# SWG.net
KiCad netlist of a schematic drawn in Altium Designer
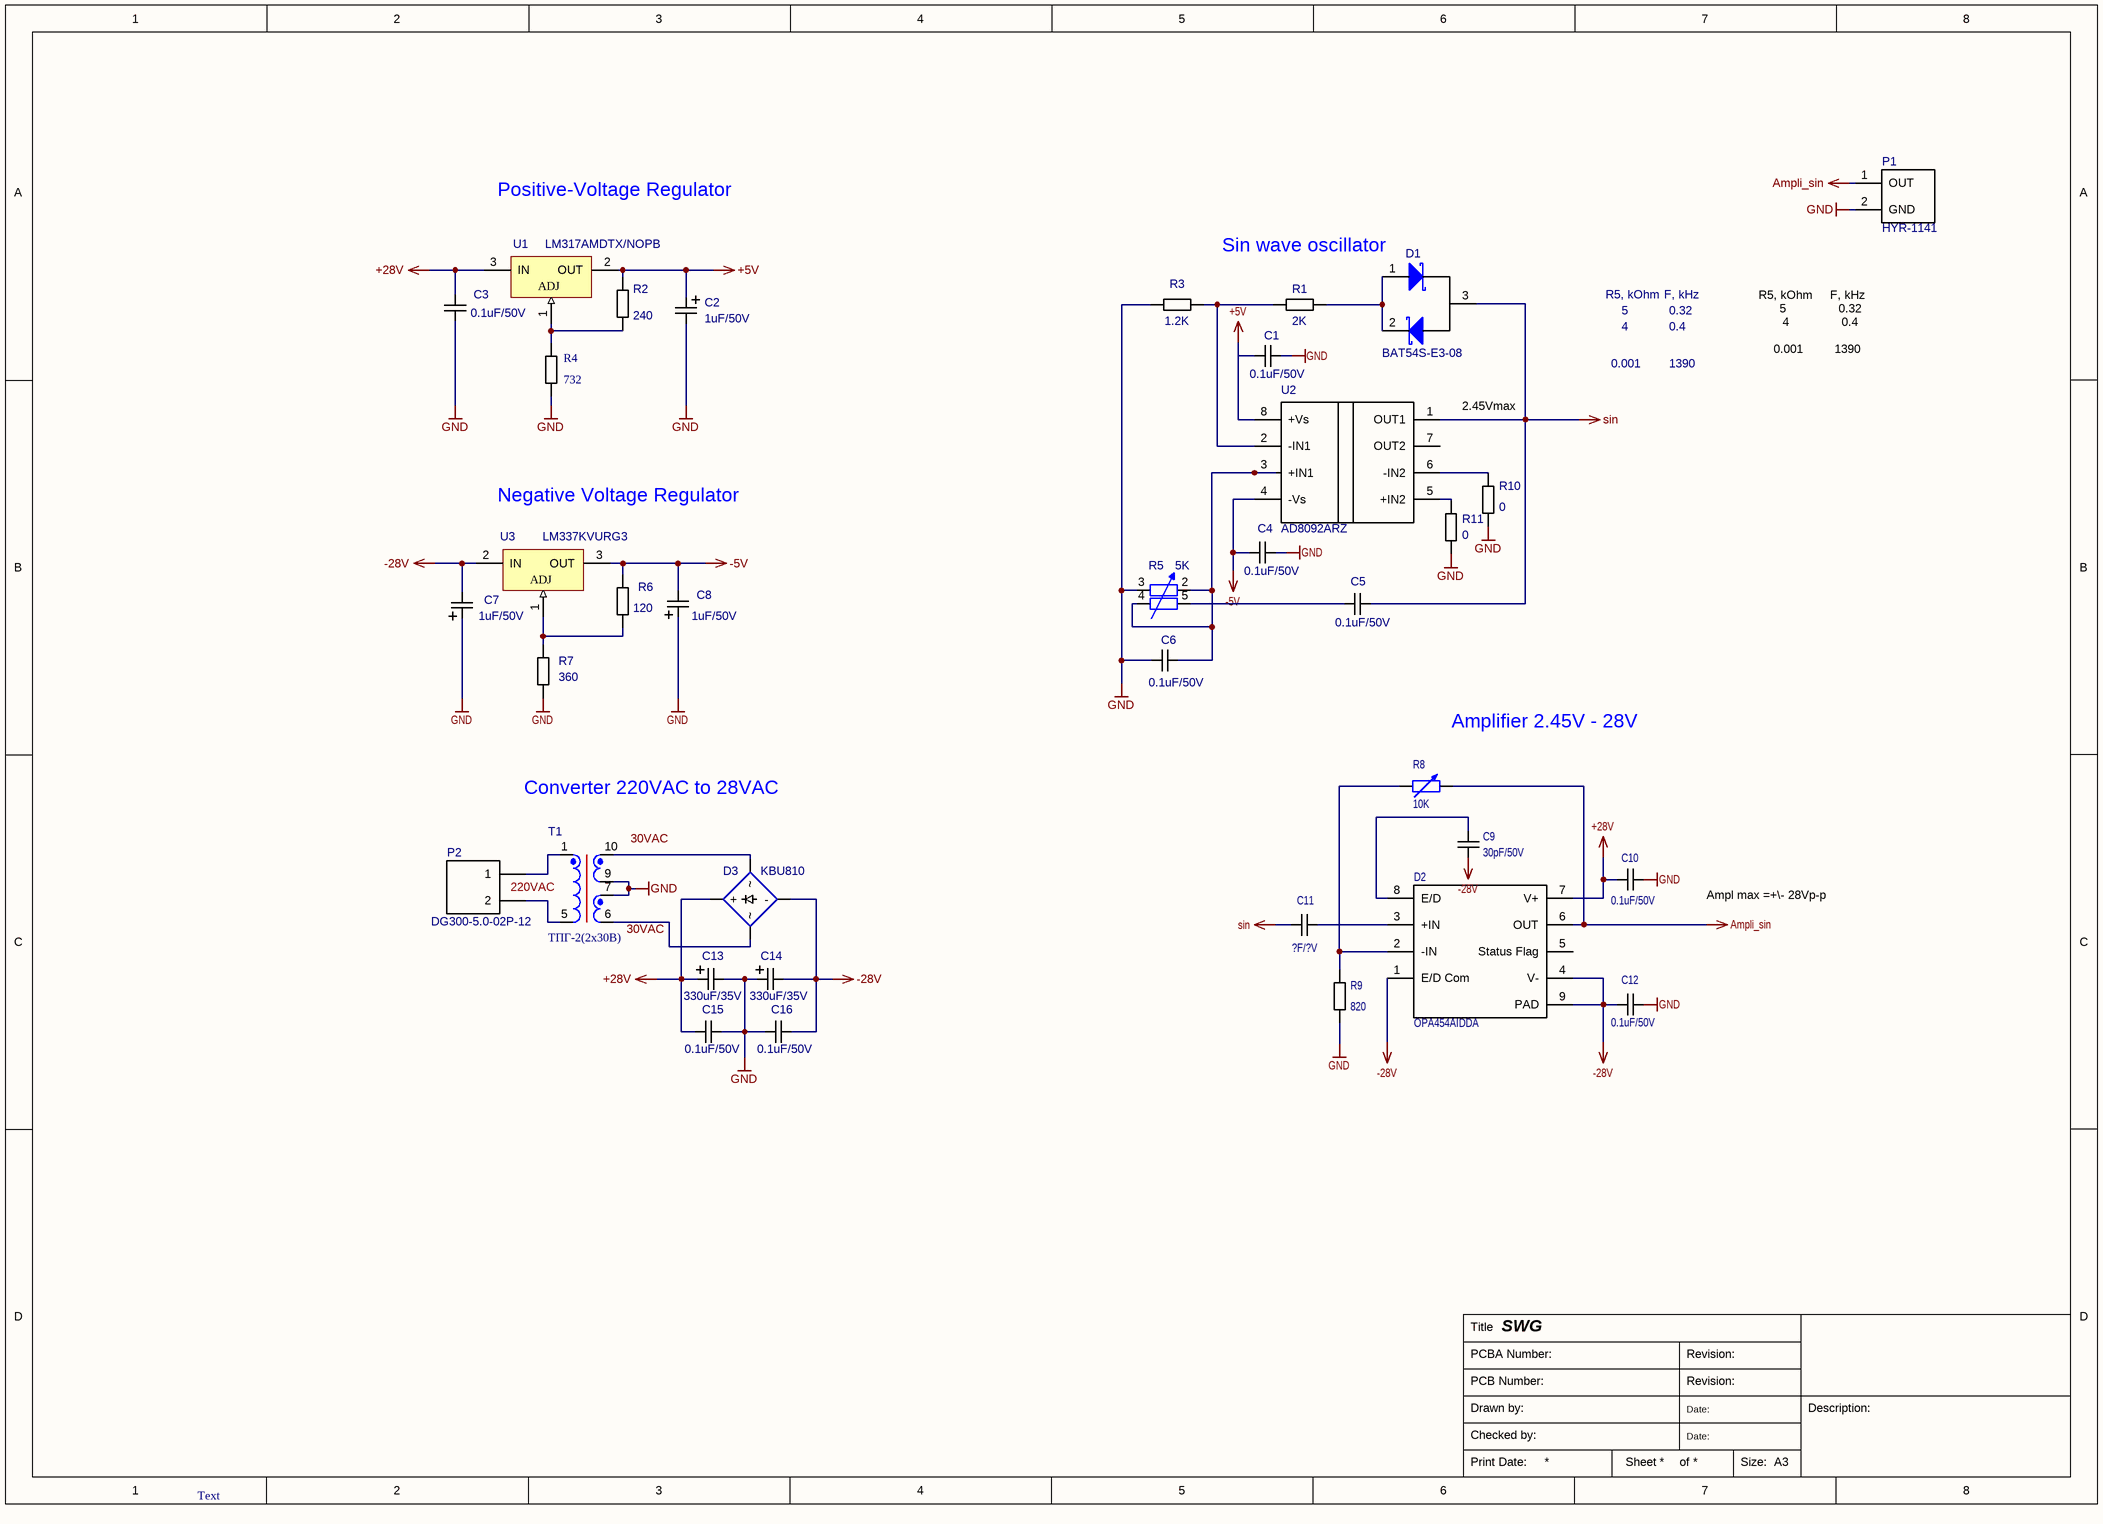
[diagram p0: SWG.SchDoc]

(export (version "E")
  (design (tool "Eeschema 10.0.6"))
  (components
    (comp (ref "C1")
      (value "0.1uF/50V")
      (footprint "C0603")
      (description "Ceramic chip capacitor. 0.1 UF X7R 50V 10% 0603")
      (fields
        (field (name "MANUFACTURER") "Murata Manufacturing")
        (field (name "PARTNUMBER") "GRM188R71H104KA93D")
      )
      (libsource (lib "Schlib_SIN_GEN") (part "CAP_0603_0.1uF/50V"))
    )
    (comp (ref "C2")
      (value "1uF/50V")
      (footprint "UCHEMI-CON_CAP0404_RAD")
      (description "Electrolytic smd capacitor 1 UF 50V")
      (fields (field (name "MANUFACTURER") "JB") (field (name "PARTNUMBER") "JCK1H010M040054"))
      (libsource (lib "Schlib_SIN_GEN") (part "CAP_electrolit_1uf"))
    )
    (comp (ref "C3")
      (value "0.1uF/50V")
      (footprint "C0603")
      (description "Ceramic chip capacitor. 0.1 UF X7R 50V 10% 0603")
      (fields
        (field (name "MANUFACTURER") "Murata Manufacturing")
        (field (name "PARTNUMBER") "GRM188R71H104KA93D")
      )
      (libsource (lib "Schlib_SIN_GEN") (part "CAP_0603_0.1uF/50V"))
    )
    (comp (ref "C4")
      (value "0.1uF/50V")
      (footprint "C0603")
      (description "Ceramic chip capacitor. 0.1 UF X7R 50V 10% 0603")
      (fields
        (field (name "MANUFACTURER") "Murata Manufacturing")
        (field (name "PARTNUMBER") "GRM188R71H104KA93D")
      )
      (libsource (lib "Schlib_SIN_GEN") (part "CAP_0603_0.1uF/50V"))
    )
    (comp (ref "C5")
      (value "0.1uF/50V")
      (footprint "C0603")
      (fields
        (field (name "MANUFACTURER") "Murata Manufacturing")
        (field (name "PARTNUMBER") "GRM188R71H104KA93D")
      )
      (libsource (lib "Schlib_SIN_GEN") (part "CAP_0603_0.1F/50V"))
    )
    (comp (ref "C6")
      (value "0.1uF/50V")
      (footprint "C0603")
      (description "Ceramic chip capacitor. 0.1 UF X7R 50V 10% 0603")
      (fields
        (field (name "MANUFACTURER") "Murata Manufacturing")
        (field (name "PARTNUMBER") "GRM188R71H104KA93D")
      )
      (libsource (lib "Schlib_SIN_GEN") (part "CAP_0603_0.1uF/50V"))
    )
    (comp (ref "C7")
      (value "1uF/50V")
      (footprint "UCHEMI-CON_CAP0404_RAD")
      (description "Electrolytic smd capacitor 1 UF 50V")
      (fields (field (name "MANUFACTURER") "JB") (field (name "PARTNUMBER") "JCK1H010M040054"))
      (libsource (lib "Schlib_SIN_GEN") (part "CAP_electrolit_1uf"))
    )
    (comp (ref "C8")
      (value "1uF/50V")
      (footprint "UCHEMI-CON_CAP0404_RAD")
      (description "Electrolytic smd capacitor 1 UF 50V")
      (fields (field (name "MANUFACTURER") "JB") (field (name "PARTNUMBER") "JCK1H010M040054"))
      (libsource (lib "Schlib_SIN_GEN") (part "CAP_electrolit_1uf"))
    )
    (comp (ref "C9")
      (value "30pF/50V")
      (footprint "C0603")
      (fields
        (field (name "MANUFACTURER") "Murata Manufacturing")
        (field (name "PARTNUMBER") "GRM2165C1H300JZ01D")
      )
      (libsource (lib "Schlib_SIN_GEN") (part "CAP_0603_30pF/50V"))
    )
    (comp (ref "C10")
      (value "0.1uF/50V")
      (footprint "C0603")
      (description "Ceramic chip capacitor. 0.1 UF X7R 50V 10% 0603")
      (fields
        (field (name "MANUFACTURER") "Murata Manufacturing")
        (field (name "PARTNUMBER") "GRM188R71H104KA93D")
      )
      (libsource (lib "Schlib_SIN_GEN") (part "CAP_0603_0.1F/50V"))
    )
    (comp (ref "C11")
      (value "?F/?V")
      (footprint "C0603")
      (fields (field (name "MANUFACTURER") "Murata Manufacturing") (field (name "PARTNUMBER") "?"))
      (libsource (lib "Schlib_SIN_GEN") (part "CAP_0603_?F/?V"))
    )
    (comp (ref "C12")
      (value "0.1uF/50V")
      (footprint "C0603")
      (description "Ceramic chip capacitor. 0.1 UF X7R 50V 10% 0603")
      (fields
        (field (name "MANUFACTURER") "Murata Manufacturing")
        (field (name "PARTNUMBER") "GRM188R71H104KA93D")
      )
      (libsource (lib "Schlib_SIN_GEN") (part "CAP_0603_0.1F/50V"))
    )
    (comp (ref "C13")
      (value "330uF/35V")
      (footprint "UCHEMI-CON_CAP1010_RAD")
      (fields (field (name "MANUFACTURER") "JB") (field (name "PARTNUMBER") "JCK1V331M100105"))
      (libsource (lib "Schlib_SIN_GEN") (part "CAP_electrolit_330uf"))
    )
    (comp (ref "C14")
      (value "330uF/35V")
      (footprint "UCHEMI-CON_CAP1010_RAD")
      (fields (field (name "MANUFACTURER") "JB") (field (name "PARTNUMBER") "JCK1V331M100105"))
      (libsource (lib "Schlib_SIN_GEN") (part "CAP_electrolit_330uf"))
    )
    (comp (ref "C15")
      (value "0.1uF/50V")
      (footprint "C0603")
      (description "Ceramic chip capacitor. 0.1 UF X7R 50V 10% 0603")
      (fields
        (field (name "MANUFACTURER") "Murata Manufacturing")
        (field (name "PARTNUMBER") "GRM188R71H104KA93D")
      )
      (libsource (lib "Schlib_SIN_GEN") (part "CAP_0603_0.1F/50V"))
    )
    (comp (ref "C16")
      (value "0.1uF/50V")
      (footprint "C0603")
      (description "Ceramic chip capacitor. 0.1 UF X7R 50V 10% 0603")
      (fields
        (field (name "MANUFACTURER") "Murata Manufacturing")
        (field (name "PARTNUMBER") "GRM188R71H104KA93D")
      )
      (libsource (lib "Schlib_SIN_GEN") (part "CAP_0603_0.1F/50V"))
    )
    (comp (ref "D1")
      (value "BAT54S-E3-08")
      (footprint "SOT23-3L")
      (description "Dual Schottky Rectifier, SOT-23, 30V 200mA")
      (fields (field (name "MANUFACTURER") "Vishay"))
      (libsource (lib "Schlib_SIN_GEN") (part "Diode BAT54S"))
    )
    (comp (ref "D2")
      (value "OPA454AIDDA")
      (footprint "TI_8SOICPAD")
      (description "IC OPAMP GP 1 CIRCUIT 8SOPWRPAD")
      (fields (field (name "MANUFACTURER") "Texas Instruments"))
      (libsource (lib "Schlib_SIN_GEN") (part "CH_OPA454AIDDA"))
    )
    (comp (ref "D3")
      (value "KBU810")
      (footprint "KBU8")
      (description "KBU8 series bridge single-phase rectifier, 8А, 1000V")
      (fields (field (name "MANUFACTURER") "China"))
      (libsource (lib "Schlib_SIN_GEN") (part "KBU810"))
    )
    (comp (ref "P1")
      (value "HYR-1141")
      (footprint "SMA")
      (fields (field (name "MANUFACTURER") "New Centress (HOYUTEC)"))
      (libsource (lib "Schlib_SIN_GEN") (part "SMA"))
    )
    (comp (ref "P2")
      (value "DG300-5.0-02P-12")
      (footprint "DG300-5.0-02P-12")
      (fields (field (name "MANUFACTURER") "Degson Electronics"))
      (libsource (lib "Schlib_SIN_GEN") (part "DG300-5.0-02P-12"))
    )
    (comp (ref "R1")
      (value "2K")
      (footprint "R0603")
      (fields (field (name "MANUFACTURER") "Yageo") (field (name "PARTNUMBER") "RC0603FR-0744K2L"))
      (libsource (lib "Schlib_SIN_GEN") (part "RES_0603_2K"))
    )
    (comp (ref "R2")
      (value "240")
      (footprint "SWG:R0603")
      (description "RES SMD 240 OHM 1% 1/10W 0603")
      (fields
        (field (name "MANUFACTURER") "Panasonic Electronic Components")
        (field (name "PARTNUMBER") "ERJ-3EKF2400V")
      )
      (libsource (lib "SWG") (part "RES_0402_240"))
    )
    (comp (ref "R3")
      (value "1.2K")
      (footprint "R0603")
      (fields (field (name "MANUFACTURER") "Yageo") (field (name "PARTNUMBER") "RC0603FR-071K2L"))
      (libsource (lib "Schlib_SIN_GEN") (part "RES_0603_1.2K"))
    )
    (comp (ref "R4")
      (value "732")
      (footprint "SWG:R0603")
      (description "RES SMD 732 OHM 1% 1/10W 0603")
      (fields
        (field (name "MANUFACTURER") "Panasonic Electronic Components")
        (field (name "PARTNUMBER") "ERJ-3EKF7320V")
      )
      (libsource (lib "SWG") (part "RES_0402_732"))
    )
    (comp (ref "R5")
      (value "5K")
      (footprint "RES_Adj_duble_5K")
      (description "Dual variable resistor WH148-2, resistance nominal 5kom. Metal handle with a recess for the cap.")
      (fields (field (name "PARTNUMBER") "WH148-2") (field (name "MANUFACTURER") "China"))
      (libsource (lib "Schlib_SIN_GEN") (part "RES_Adj_duble_5K"))
    )
    (comp (ref "R6")
      (value "120")
      (footprint "SWG:R0603")
      (fields
        (field (name "MANUFACTURER") "Panasonic Electronic Components Panasonic Electronic Components")
        (field (name "PARTNUMBER") "ERJ-2RKF1200X")
        (field (name "TOLERANCE") "±1%")
      )
      (libsource (lib "SWG") (part "RES_0402"))
    )
    (comp (ref "R7")
      (value "360")
      (footprint "SWG:R0603")
      (description "RES SMD 360 OHM 1% 1/10W 0603")
      (fields
        (field (name "MANUFACTURER") "Panasonic Electronic Components")
        (field (name "PARTNUMBER") "ERJ-3EKF3600V")
      )
      (libsource (lib "SWG") (part "RES_0402"))
    )
    (comp (ref "R8")
      (value "10K")
      (footprint "RES_Adj_10K")
      (description "Variable Resistor")
      (fields (field (name "PARTNUMBER") "16K1-10C10K,L15KC") (field (name "MANUFACTURER") "China"))
      (libsource (lib "Schlib_SIN_GEN") (part "Res_Adj_10K"))
    )
    (comp (ref "R9")
      (value "820")
      (footprint "R0603")
      (fields (field (name "MANUFACTURER") "Yageo") (field (name "PARTNUMBER") "RC0603FR-07820RL"))
      (libsource (lib "Schlib_SIN_GEN") (part "RES_0603_820"))
    )
    (comp (ref "R10")
      (value "0")
      (footprint "R0603")
      (fields (field (name "MANUFACTURER") "Yageo") (field (name "PARTNUMBER") "RC0603JR-070RL"))
      (libsource (lib "Schlib_SIN_GEN") (part "RES_0603_0"))
    )
    (comp (ref "R11")
      (value "0")
      (footprint "R0603")
      (fields (field (name "MANUFACTURER") "Yageo") (field (name "PARTNUMBER") "RC0603JR-070RL"))
      (libsource (lib "Schlib_SIN_GEN") (part "RES_0603_0"))
    )
    (comp (ref "T1")
      (value "ТПГ-2(2х30В)")
      (footprint "ТПГ-2 (2x30)")
      (description "Sealed transformer")
      (fields (field (name "MANUFACTURER") "Комплекс"))
      (libsource (lib "Schlib_SIN_GEN") (part "ТПГ-2 (2x30)"))
    )
    (comp (ref "U1")
      (value "LM317AMDTX/NOPB")
      (footprint "SC_TO-252A")
      (description "3-Terminal Adjustable Regulator")
      (fields (field (name "MANUFACTURER") "Texas Instruments"))
      (libsource (lib "Schlib_SIN_GEN") (part "LM317AMDTX/NOPB"))
    )
    (comp (ref "U2")
      (value "AD8092ARZ")
      (footprint "AD_SOIC-8_R-8_Rev4")
      (fields (field (name "MANUFACTURER") "Analog Devices"))
      (libsource (lib "Schlib_SIN_GEN") (part "AD8092ARZ_1"))
    )
    (comp (ref "U3")
      (value "LM337KVURG3")
      (footprint "SC_TO-252A")
      (description "3-Terminal Adjustable Negative Regulator")
      (fields (field (name "MANUFACTURER") "Texas Instruments"))
      (libsource (lib "Schlib_SIN_GEN") (part "LM337KVURG3"))
    )
  )
  (nets
    (net (code "1") (name "+5V") (class "Default")
      (node (ref "C1") (pin "1") (pinfunction "1_1") (pintype "passive"))
      (node (ref "C2") (pin "1") (pinfunction "+_1") (pintype "passive"))
      (node (ref "R2") (pin "2") (pinfunction "2_2") (pintype "passive"))
      (node (ref "U1") (pin "2") (pinfunction "OUT_2") (pintype "power_in"))
      (node (ref "U2") (pin "8") (pinfunction "+Vs_8") (pintype "passive"))
    )
    (net (code "2") (name "+28V") (class "Default")
      (node (ref "C10") (pin "1") (pinfunction "1_1") (pintype "passive"))
      (node (ref "C13") (pin "1") (pinfunction "+_1") (pintype "passive"))
      (node (ref "C15") (pin "1") (pinfunction "1_1") (pintype "passive"))
      (node (ref "C3") (pin "2") (pinfunction "2_2") (pintype "passive"))
      (node (ref "D2") (pin "7") (pinfunction "V+_7") (pintype "passive"))
      (node (ref "D3") (pin "1") (pinfunction "+_1") (pintype "passive"))
      (node (ref "U1") (pin "3") (pinfunction "IN_3") (pintype "power_in"))
    )
    (net (code "3") (name "-5V") (class "Default")
      (node (ref "C4") (pin "1") (pinfunction "1_1") (pintype "passive"))
      (node (ref "C8") (pin "2") (pinfunction "-_2") (pintype "passive"))
      (node (ref "R6") (pin "2") (pinfunction "2_2") (pintype "passive"))
      (node (ref "U2") (pin "4") (pinfunction "-Vs_4") (pintype "passive"))
      (node (ref "U3") (pin "3") (pinfunction "OUT_3") (pintype "power_in"))
    )
    (net (code "4") (name "-28V") (class "Default")
      (node (ref "C12") (pin "1") (pinfunction "1_1") (pintype "passive"))
      (node (ref "C14") (pin "2") (pinfunction "-_2") (pintype "passive"))
      (node (ref "C16") (pin "2") (pinfunction "2_2") (pintype "passive"))
      (node (ref "C7") (pin "2") (pinfunction "-_2") (pintype "passive"))
      (node (ref "C9") (pin "2") (pinfunction "2_2") (pintype "passive"))
      (node (ref "D2") (pin "1") (pinfunction "E/D_Com_1") (pintype "passive"))
      (node (ref "D2") (pin "4") (pinfunction "V-_4") (pintype "passive"))
      (node (ref "D2") (pin "9") (pinfunction "PAD_9") (pintype "passive"))
      (node (ref "D3") (pin "4") (pinfunction "-_4") (pintype "passive"))
      (node (ref "U3") (pin "2") (pinfunction "IN_2") (pintype "power_in"))
    )
    (net (code "6") (name "Ampli_sin") (class "Default")
      (node (ref "D2") (pin "6") (pinfunction "OUT_6") (pintype "passive"))
      (node (ref "P1") (pin "1") (pinfunction "OUT_1") (pintype "passive"))
      (node (ref "R8") (pin "2") (pinfunction "2_2") (pintype "passive"))
    )
    (net (code "7") (name "GND") (class "Default")
      (node (ref "C1") (pin "2") (pinfunction "2_2") (pintype "passive"))
      (node (ref "C10") (pin "2") (pinfunction "2_2") (pintype "passive"))
      (node (ref "C12") (pin "2") (pinfunction "2_2") (pintype "passive"))
      (node (ref "C13") (pin "2") (pinfunction "-_2") (pintype "passive"))
      (node (ref "C14") (pin "1") (pinfunction "+_1") (pintype "passive"))
      (node (ref "C15") (pin "2") (pinfunction "2_2") (pintype "passive"))
      (node (ref "C16") (pin "1") (pinfunction "1_1") (pintype "passive"))
      (node (ref "C2") (pin "2") (pinfunction "-_2") (pintype "passive"))
      (node (ref "C3") (pin "1") (pinfunction "1_1") (pintype "passive"))
      (node (ref "C4") (pin "2") (pinfunction "2_2") (pintype "passive"))
      (node (ref "C6") (pin "1") (pinfunction "1_1") (pintype "passive"))
      (node (ref "C7") (pin "1") (pinfunction "+_1") (pintype "passive"))
      (node (ref "C8") (pin "1") (pinfunction "+_1") (pintype "passive"))
      (node (ref "P1") (pin "2") (pinfunction "GND_2") (pintype "passive"))
      (node (ref "R10") (pin "2") (pinfunction "2_2") (pintype "passive"))
      (node (ref "R11") (pin "2") (pinfunction "2_2") (pintype "passive"))
      (node (ref "R3") (pin "1") (pinfunction "1_1") (pintype "passive"))
      (node (ref "R4") (pin "1") (pinfunction "1_1") (pintype "passive"))
      (node (ref "R5") (pin "3") (pinfunction "1_3") (pintype "passive"))
      (node (ref "R7") (pin "1") (pinfunction "1_1") (pintype "passive"))
      (node (ref "R9") (pin "1") (pinfunction "1_1") (pintype "passive"))
      (node (ref "T1") (pin "7") (pinfunction "7_7") (pintype "passive"))
      (node (ref "T1") (pin "9") (pinfunction "9_9") (pintype "passive"))
    )
    (net (code "8") (name "Net-(D1-A1)") (class "Default")
      (node (ref "D1") (pin "1") (pinfunction "A1_1") (pintype "passive"))
      (node (ref "D1") (pin "2") (pinfunction "K2_2") (pintype "passive"))
      (node (ref "R1") (pin "2") (pinfunction "2_2") (pintype "passive"))
    )
    (net (code "9") (name "Net-(D2-+IN)") (class "Default")
      (node (ref "C11") (pin "2") (pinfunction "2_2") (pintype "passive"))
      (node (ref "D2") (pin "3") (pinfunction "+IN_3") (pintype "passive"))
    )
    (net (code "10") (name "Net-(D2--IN)") (class "Default")
      (node (ref "D2") (pin "2") (pinfunction "-IN_2") (pintype "passive"))
      (node (ref "R8") (pin "1") (pinfunction "1_1") (pintype "passive"))
      (node (ref "R9") (pin "2") (pinfunction "2_2") (pintype "passive"))
    )
    (net (code "11") (name "Net-(D2-E{slash}D)") (class "Default")
      (node (ref "C9") (pin "1") (pinfunction "1_1") (pintype "passive"))
      (node (ref "D2") (pin "8") (pinfunction "E/D_8") (pintype "passive"))
    )
    (net (code "12") (name "Net-(D3-~-Pad2)") (class "Default")
      (node (ref "D3") (pin "2") (pinfunction "~_2") (pintype "passive"))
      (node (ref "T1") (pin "10") (pinfunction "10_10") (pintype "passive"))
    )
    (net (code "13") (name "Net-(D3-~-Pad3)") (class "Default")
      (node (ref "D3") (pin "3") (pinfunction "~_3") (pintype "passive"))
      (node (ref "T1") (pin "6") (pinfunction "6_6") (pintype "passive"))
    )
    (net (code "14") (name "Net-(P2-Pad1)") (class "Default")
      (node (ref "P2") (pin "1") (pinfunction "1_1") (pintype "passive"))
      (node (ref "T1") (pin "1") (pinfunction "1_1") (pintype "passive"))
    )
    (net (code "15") (name "Net-(P2-Pad2)") (class "Default")
      (node (ref "P2") (pin "2") (pinfunction "2_2") (pintype "passive"))
      (node (ref "T1") (pin "5") (pinfunction "5_5") (pintype "passive"))
    )
    (net (code "16") (name "Net-(R5-3)") (class "Default")
      (node (ref "C6") (pin "2") (pinfunction "2_2") (pintype "passive"))
      (node (ref "R5") (pin "2") (pinfunction "2_2") (pintype "passive"))
      (node (ref "R5") (pin "4") (pinfunction "3_4") (pintype "passive"))
      (node (ref "U2") (pin "3") (pinfunction "+IN1_3") (pintype "passive"))
    )
    (net (code "17") (name "Net-(R5-4)") (class "Default")
      (node (ref "C5") (pin "1") (pinfunction "1_1") (pintype "passive"))
      (node (ref "R5") (pin "5") (pinfunction "4_5") (pintype "passive"))
    )
    (net (code "18") (name "Net-(U1-ADJ)") (class "Default")
      (node (ref "R2") (pin "1") (pinfunction "1_1") (pintype "passive"))
      (node (ref "R4") (pin "2") (pinfunction "2_2") (pintype "passive"))
      (node (ref "U1") (pin "1") (pinfunction "ADJ_1") (pintype "input"))
    )
    (net (code "19") (name "Net-(U2-+IN2)") (class "Default")
      (node (ref "R11") (pin "1") (pinfunction "1_1") (pintype "passive"))
      (node (ref "U2") (pin "5") (pinfunction "+IN2_5") (pintype "passive"))
    )
    (net (code "20") (name "Net-(U2--IN1)") (class "Default")
      (node (ref "R1") (pin "1") (pinfunction "1_1") (pintype "passive"))
      (node (ref "R3") (pin "2") (pinfunction "2_2") (pintype "passive"))
      (node (ref "U2") (pin "2") (pinfunction "-IN1_2") (pintype "passive"))
    )
    (net (code "21") (name "Net-(U2--IN2)") (class "Default")
      (node (ref "R10") (pin "1") (pinfunction "1_1") (pintype "passive"))
      (node (ref "U2") (pin "6") (pinfunction "-IN2_6") (pintype "passive"))
    )
    (net (code "22") (name "Net-(U3-ADJ)") (class "Default")
      (node (ref "R6") (pin "1") (pinfunction "1_1") (pintype "passive"))
      (node (ref "R7") (pin "2") (pinfunction "2_2") (pintype "passive"))
      (node (ref "U3") (pin "1") (pinfunction "ADJ_1") (pintype "input"))
    )
    (net (code "23") (name "sin") (class "Default")
      (node (ref "C11") (pin "1") (pinfunction "1_1") (pintype "passive"))
      (node (ref "C5") (pin "2") (pinfunction "2_2") (pintype "passive"))
      (node (ref "D1") (pin "3") (pinfunction "K1A2_3") (pintype "passive"))
      (node (ref "U2") (pin "1") (pinfunction "OUT1_1") (pintype "passive"))
    )
    (net (code "24") (name "unconnected-(D2-Status_Flag-Pad5)") (class "Default")
      (node (ref "D2") (pin "5") (pinfunction "Status_Flag_5") (pintype "passive"))
    )
    (net (code "25") (name "unconnected-(U2-OUT2-Pad7)") (class "Default")
      (node (ref "U2") (pin "7") (pinfunction "OUT2_7") (pintype "passive"))
    )
  )
)
